# relay.net
KiCad netlist of a schematic drawn in EAGLE
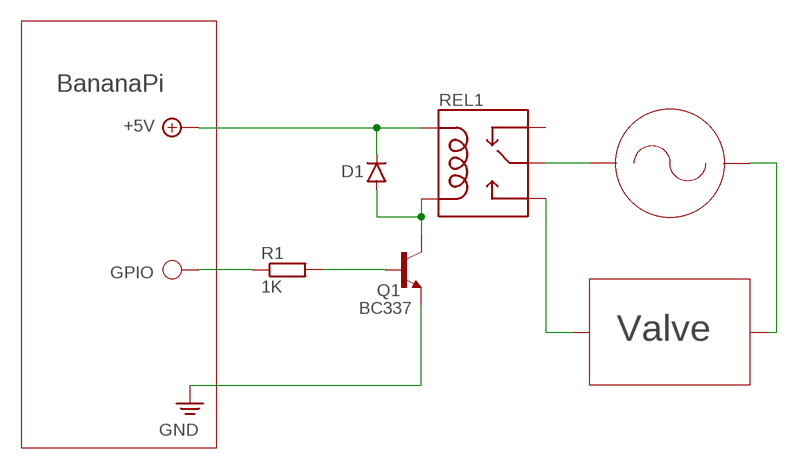
[diagram p0: schematic, sheet 1]

(export (version "E")
  (design (tool "Eeschema 10.0.6"))
  (components
    (comp (ref "D1")
      (value "DIODE")
      (footprint "eagle-import:DIODE-1N4001-KIT")
      (libsource (lib "eagle-import") (part "DIODE"))
    )
    (comp (ref "Q1")
      (value "BC337")
      (footprint "eagle-import:TO92")
      (libsource (lib "eagle-import") (part "BC337"))
    )
    (comp (ref "R1")
      (value "1K")
      (footprint "eagle-import:0207_15")
      (libsource (lib "eagle-import") (part "R-EU_0207/15"))
    )
    (comp (ref "REL1")
      (value "RELAYPTH")
      (footprint "eagle-import:RELAY-G5Q")
      (libsource (lib "eagle-import") (part "RELAYPTH"))
    )
  )
  (nets
    (net (code "1") (name "+5V") (class "Default")
      (node (ref "D1") (pin "C") (pinfunction "C_C") (pintype "passive"))
      (node (ref "REL1") (pin "5") (pinfunction "COIL1_5") (pintype "bidirectional"))
    )
    (net (code "2") (name "GND") (class "Default")
      (node (ref "Q1") (pin "1") (pinfunction "E_1") (pintype "passive"))
    )
    (net (code "3") (name "Net-(Q1-B)") (class "Default")
      (node (ref "Q1") (pin "2") (pinfunction "B_2") (pintype "passive"))
      (node (ref "R1") (pin "2") (pinfunction "2_2") (pintype "passive"))
    )
    (net (code "4") (name "Net-(Q1-C)") (class "Default")
      (node (ref "D1") (pin "A") (pinfunction "A_A") (pintype "passive"))
      (node (ref "Q1") (pin "3") (pinfunction "C_3") (pintype "passive"))
      (node (ref "REL1") (pin "1") (pinfunction "COIL2_1") (pintype "bidirectional"))
    )
    (net (code "5") (name "unconnected-(R1-Pad1)") (class "Default")
      (node (ref "R1") (pin "1") (pinfunction "1_1") (pintype "passive"))
    )
    (net (code "6") (name "unconnected-(REL1-MAIN-Pad2)") (class "Default")
      (node (ref "REL1") (pin "2") (pinfunction "MAIN_2") (pintype "bidirectional"))
    )
    (net (code "7") (name "unconnected-(REL1-NC-Pad4)") (class "Default")
      (node (ref "REL1") (pin "4") (pinfunction "NC_4") (pintype "bidirectional"))
    )
    (net (code "8") (name "unconnected-(REL1-NO-Pad3)") (class "Default")
      (node (ref "REL1") (pin "3") (pinfunction "NO_3") (pintype "bidirectional"))
    )
  )
)
